# IoTKitV3th.net
KiCad netlist of a schematic drawn in EAGLE
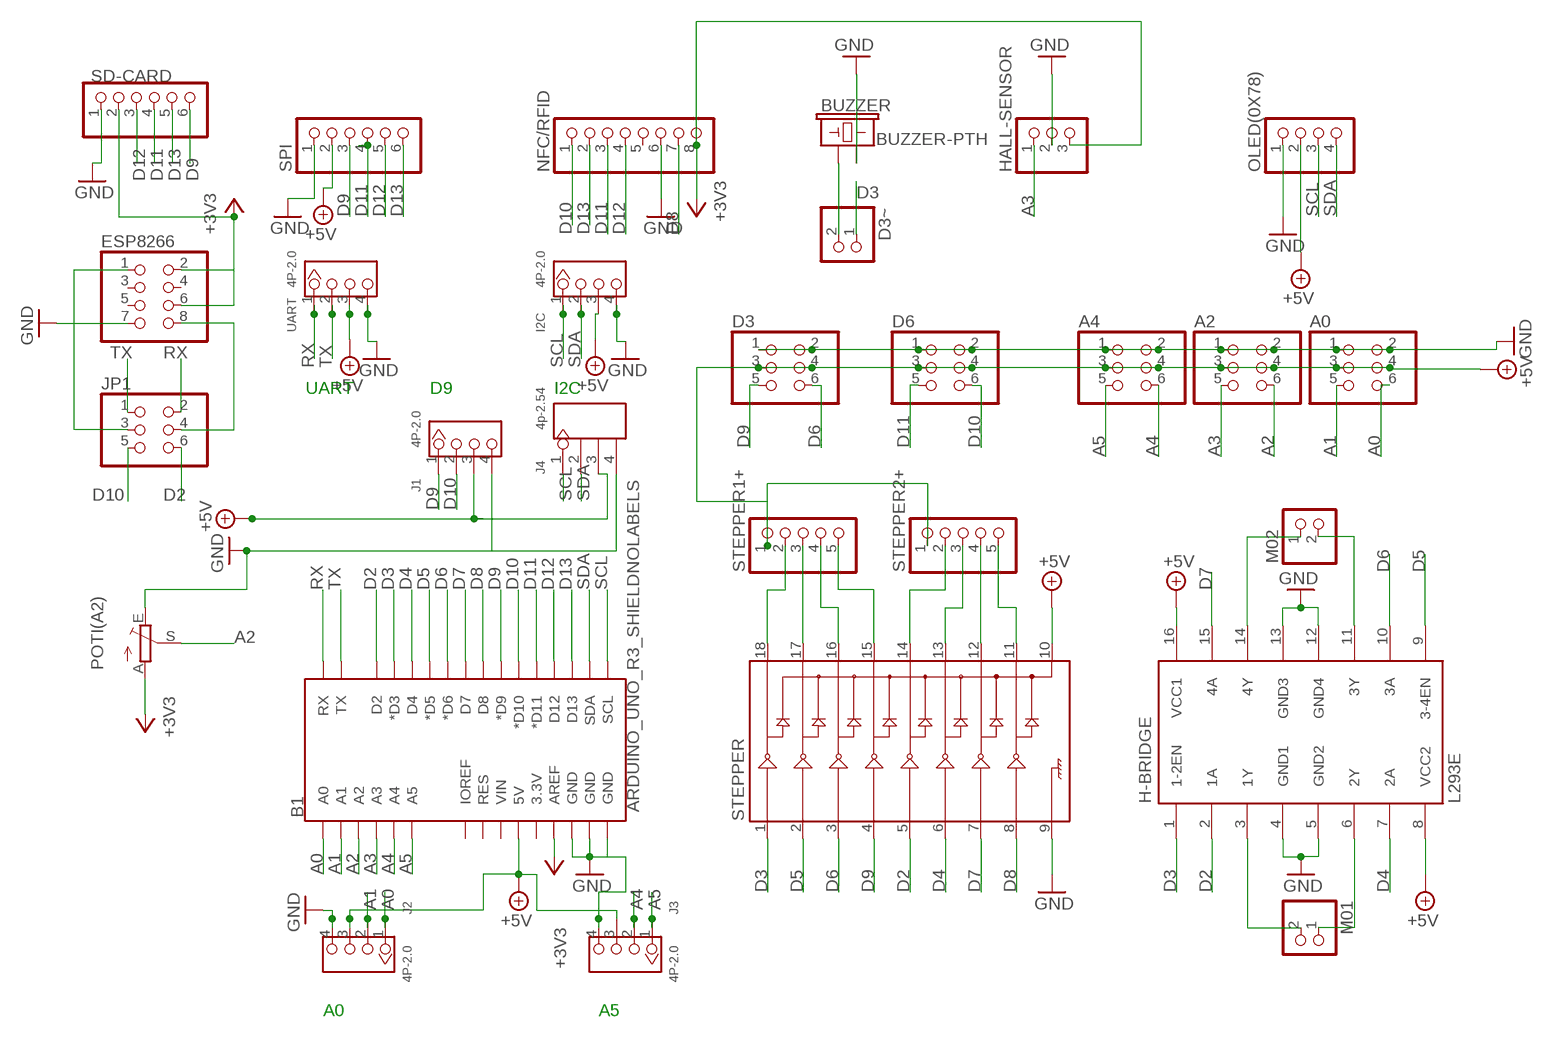
[diagram p0: schematic, sheet 1]

(export (version "E")
  (design (tool "Eeschema 10.0.6"))
  (components
    (comp (ref "A0")
      (value "PINHD-2X3")
      (footprint "eagle-import:2X03")
      (libsource (lib "eagle-import") (part "PINHD-2X3"))
    )
    (comp (ref "A2")
      (value "PINHD-2X3")
      (footprint "eagle-import:2X03")
      (libsource (lib "eagle-import") (part "PINHD-2X3"))
    )
    (comp (ref "A4")
      (value "PINHD-2X3")
      (footprint "eagle-import:2X03")
      (libsource (lib "eagle-import") (part "PINHD-2X3"))
    )
    (comp (ref "B1")
      (value "ARDUINO_UNO_R3_SHIELDNOLABELS")
      (footprint "eagle-import:UNO_R3_SHIELD_NOLABELS")
      (libsource (lib "eagle-import") (part "ARDUINO_UNO_R3_SHIELDNOLABELS"))
    )
    (comp (ref "BUZZER")
      (value "BUZZER-PTH")
      (footprint "eagle-import:BUZZER-12MM")
      (libsource (lib "eagle-import") (part "BUZZER-PTH"))
    )
    (comp (ref "D3")
      (value "PINHD-2X3")
      (footprint "eagle-import:2X03")
      (libsource (lib "eagle-import") (part "PINHD-2X3"))
    )
    (comp (ref "D3~")
      (value "PINHD-1X2")
      (footprint "eagle-import:1X02")
      (libsource (lib "eagle-import") (part "PINHD-1X2"))
    )
    (comp (ref "D6")
      (value "PINHD-2X3")
      (footprint "eagle-import:2X03")
      (libsource (lib "eagle-import") (part "PINHD-2X3"))
    )
    (comp (ref "ESP8266")
      (value "PINHD-2X4")
      (footprint "eagle-import:2X04")
      (libsource (lib "eagle-import") (part "PINHD-2X4"))
    )
    (comp (ref "H-BRIDGE")
      (value "L293E")
      (footprint "eagle-import:DIL16")
      (fields (field (name "MF") "Arrow Electronics"))
      (libsource (lib "eagle-import") (part "L293E"))
    )
    (comp (ref "HALL-SENSOR")
      (value "PINHD-1X3")
      (footprint "eagle-import:1X03")
      (libsource (lib "eagle-import") (part "PINHD-1X3"))
    )
    (comp (ref "I2C")
      (value "4P-2.0")
      (footprint "eagle-import:HW4-2.0")
      (libsource (lib "eagle-import") (part "GROVE-CONNECTOR-DIP(4P-2.0)"))
    )
    (comp (ref "J1")
      (value "4P-2.0")
      (footprint "eagle-import:HW4-2.0")
      (libsource (lib "eagle-import") (part "GROVE-CONNECTOR-DIP(4P-2.0)"))
    )
    (comp (ref "J2")
      (value "4P-2.0")
      (footprint "eagle-import:HW4-2.0")
      (libsource (lib "eagle-import") (part "GROVE-CONNECTOR-DIP(4P-2.0)"))
    )
    (comp (ref "J3")
      (value "4P-2.0")
      (footprint "eagle-import:HW4-2.0")
      (libsource (lib "eagle-import") (part "GROVE-CONNECTOR-DIP(4P-2.0)"))
    )
    (comp (ref "J4")
      (value "4p-2.54")
      (footprint "eagle-import:H4-2.54")
      (fields (field (name "MPN") "P125-1104A0BS116A1"))
      (libsource (lib "eagle-import") (part "DIP-BLACK-MALE-HEADER-VERT(4P-2.54)"))
    )
    (comp (ref "JP1")
      (value "PINHD-2X3")
      (footprint "eagle-import:2X03")
      (libsource (lib "eagle-import") (part "pinhead_325_PINHD-2X3"))
    )
    (comp (ref "M01")
      (value "PINHD-1X2")
      (footprint "eagle-import:1X02")
      (libsource (lib "eagle-import") (part "PINHD-1X2"))
    )
    (comp (ref "M02")
      (value "PINHD-1X2")
      (footprint "eagle-import:1X02")
      (libsource (lib "eagle-import") (part "PINHD-1X2"))
    )
    (comp (ref "NFC/RFID")
      (value "PINHD-1X8")
      (footprint "eagle-import:1X08")
      (libsource (lib "eagle-import") (part "PINHD-1X8"))
    )
    (comp (ref "OLED(0X78)")
      (value "PINHD-1X4")
      (footprint "eagle-import:1X04")
      (libsource (lib "eagle-import") (part "PINHD-1X4"))
    )
    (comp (ref "POTI(A2)")
      (value "TRIM_EU-B25P")
      (footprint "eagle-import:B25P")
      (libsource (lib "eagle-import") (part "TRIM_EU-B25P"))
    )
    (comp (ref "SD-CARD")
      (value "PINHD-1X6")
      (footprint "eagle-import:1X06")
      (libsource (lib "eagle-import") (part "PINHD-1X6"))
    )
    (comp (ref "SPI")
      (value "PINHD-1X6")
      (footprint "eagle-import:1X06")
      (libsource (lib "eagle-import") (part "PINHD-1X6"))
    )
    (comp (ref "STEPPER")
      (value "ULN2803DIP")
      (footprint "eagle-import:DIL18")
      (libsource (lib "eagle-import") (part "ULN2803DIP"))
    )
    (comp (ref "STEPPER1+")
      (value "PINHD-1X5")
      (footprint "eagle-import:1X05")
      (libsource (lib "eagle-import") (part "PINHD-1X5"))
    )
    (comp (ref "STEPPER2+")
      (value "PINHD-1X5")
      (footprint "eagle-import:1X05")
      (libsource (lib "eagle-import") (part "PINHD-1X5"))
    )
    (comp (ref "UART")
      (value "4P-2.0")
      (footprint "eagle-import:HW4-2.0")
      (libsource (lib "eagle-import") (part "GROVE-CONNECTOR-DIP(4P-2.0)"))
    )
  )
  (nets
    (net (code "1") (name "+3V3") (class "Default")
      (node (ref "B1") (pin "AREF") (pinfunction "AREF_AREF") (pintype "bidirectional"))
      (node (ref "ESP8266") (pin "2") (pinfunction "2_2") (pintype "passive"))
      (node (ref "ESP8266") (pin "6") (pinfunction "6_6") (pintype "passive"))
      (node (ref "HALL-SENSOR") (pin "3") (pinfunction "3_3") (pintype "passive"))
      (node (ref "NFC/RFID") (pin "8") (pinfunction "8_8") (pintype "passive"))
      (node (ref "POTI(A2)") (pin "A") (pinfunction "A_A") (pintype "passive"))
      (node (ref "SD-CARD") (pin "2") (pinfunction "2_2") (pintype "passive"))
    )
    (net (code "2") (name "+5V") (class "Default")
      (node (ref "A0") (pin "3") (pinfunction "3_3") (pintype "passive"))
      (node (ref "A0") (pin "4") (pinfunction "4_4") (pintype "passive"))
      (node (ref "A2") (pin "3") (pinfunction "3_3") (pintype "passive"))
      (node (ref "A2") (pin "4") (pinfunction "4_4") (pintype "passive"))
      (node (ref "A4") (pin "3") (pinfunction "3_3") (pintype "passive"))
      (node (ref "A4") (pin "4") (pinfunction "4_4") (pintype "passive"))
      (node (ref "B1") (pin "5V") (pinfunction "5V_5V") (pintype "bidirectional"))
      (node (ref "D3") (pin "3") (pinfunction "3_3") (pintype "passive"))
      (node (ref "D3") (pin "4") (pinfunction "4_4") (pintype "passive"))
      (node (ref "D6") (pin "3") (pinfunction "3_3") (pintype "passive"))
      (node (ref "D6") (pin "4") (pinfunction "4_4") (pintype "passive"))
      (node (ref "H-BRIDGE") (pin "16") (pinfunction "VCC1_16") (pintype "power_in"))
      (node (ref "H-BRIDGE") (pin "8") (pinfunction "VCC2_8") (pintype "power_in"))
      (node (ref "I2C") (pin "3") (pinfunction "3_3") (pintype "bidirectional"))
      (node (ref "J1") (pin "3") (pinfunction "3_3") (pintype "bidirectional"))
      (node (ref "J2") (pin "3") (pinfunction "3_3") (pintype "bidirectional"))
      (node (ref "J3") (pin "3") (pinfunction "3_3") (pintype "bidirectional"))
      (node (ref "J4") (pin "3") (pinfunction "P$3_3") (pintype "bidirectional"))
      (node (ref "OLED(0X78)") (pin "2") (pinfunction "2_2") (pintype "passive"))
      (node (ref "SPI") (pin "2") (pinfunction "2_2") (pintype "passive"))
      (node (ref "STEPPER") (pin "10") (pinfunction "10_10") (pintype "bidirectional"))
      (node (ref "STEPPER1+") (pin "1") (pinfunction "1_1") (pintype "passive"))
      (node (ref "STEPPER2+") (pin "1") (pinfunction "1_1") (pintype "passive"))
      (node (ref "UART") (pin "3") (pinfunction "3_3") (pintype "bidirectional"))
    )
    (net (code "3") (name "/A0") (class "Default")
      (node (ref "A0") (pin "6") (pinfunction "6_6") (pintype "passive"))
      (node (ref "B1") (pin "A0") (pinfunction "A0_A0") (pintype "bidirectional"))
      (node (ref "J2") (pin "1") (pinfunction "1_1") (pintype "bidirectional"))
    )
    (net (code "4") (name "/A1") (class "Default")
      (node (ref "A0") (pin "5") (pinfunction "5_5") (pintype "passive"))
      (node (ref "B1") (pin "A1") (pinfunction "A1_A1") (pintype "bidirectional"))
      (node (ref "J2") (pin "2") (pinfunction "2_2") (pintype "bidirectional"))
    )
    (net (code "5") (name "/A2") (class "Default")
      (node (ref "A2") (pin "6") (pinfunction "6_6") (pintype "passive"))
      (node (ref "B1") (pin "A2") (pinfunction "A2_A2") (pintype "bidirectional"))
      (node (ref "POTI(A2)") (pin "S") (pinfunction "S_S") (pintype "passive"))
    )
    (net (code "6") (name "/A3") (class "Default")
      (node (ref "A2") (pin "5") (pinfunction "5_5") (pintype "passive"))
      (node (ref "B1") (pin "A3") (pinfunction "A3_A3") (pintype "bidirectional"))
      (node (ref "HALL-SENSOR") (pin "1") (pinfunction "1_1") (pintype "passive"))
    )
    (net (code "7") (name "/A4") (class "Default")
      (node (ref "A4") (pin "6") (pinfunction "6_6") (pintype "passive"))
      (node (ref "B1") (pin "A4") (pinfunction "A4_A4") (pintype "bidirectional"))
      (node (ref "J3") (pin "2") (pinfunction "2_2") (pintype "bidirectional"))
    )
    (net (code "8") (name "/A5") (class "Default")
      (node (ref "A4") (pin "5") (pinfunction "5_5") (pintype "passive"))
      (node (ref "B1") (pin "A5") (pinfunction "A5_A5") (pintype "bidirectional"))
      (node (ref "J3") (pin "1") (pinfunction "1_1") (pintype "bidirectional"))
    )
    (net (code "9") (name "/D2") (class "Default")
      (node (ref "B1") (pin "D2") (pinfunction "D2_D2") (pintype "bidirectional"))
      (node (ref "H-BRIDGE") (pin "2") (pinfunction "1A_2") (pintype "input"))
      (node (ref "JP1") (pin "6") (pinfunction "6_6") (pintype "passive"))
      (node (ref "STEPPER") (pin "5") (pinfunction "5_5") (pintype "bidirectional"))
    )
    (net (code "10") (name "/D3") (class "Default")
      (node (ref "B1") (pin "D3") (pinfunction "*D3_D3") (pintype "bidirectional"))
      (node (ref "D3~") (pin "1") (pinfunction "1_1") (pintype "passive"))
      (node (ref "H-BRIDGE") (pin "1") (pinfunction "1-2EN_1") (pintype "input"))
      (node (ref "STEPPER") (pin "1") (pinfunction "1_1") (pintype "bidirectional"))
    )
    (net (code "11") (name "/D4") (class "Default")
      (node (ref "B1") (pin "D4") (pinfunction "D4_D4") (pintype "bidirectional"))
      (node (ref "H-BRIDGE") (pin "7") (pinfunction "2A_7") (pintype "input"))
      (node (ref "STEPPER") (pin "6") (pinfunction "6_6") (pintype "bidirectional"))
    )
    (net (code "12") (name "/D5") (class "Default")
      (node (ref "B1") (pin "D5") (pinfunction "*D5_D5") (pintype "bidirectional"))
      (node (ref "H-BRIDGE") (pin "9") (pinfunction "3-4EN_9") (pintype "input"))
      (node (ref "STEPPER") (pin "2") (pinfunction "2_2") (pintype "bidirectional"))
    )
    (net (code "13") (name "/D6") (class "Default")
      (node (ref "B1") (pin "D6") (pinfunction "*D6_D6") (pintype "bidirectional"))
      (node (ref "D3") (pin "6") (pinfunction "6_6") (pintype "passive"))
      (node (ref "H-BRIDGE") (pin "10") (pinfunction "3A_10") (pintype "input"))
      (node (ref "STEPPER") (pin "3") (pinfunction "3_3") (pintype "bidirectional"))
    )
    (net (code "14") (name "/D7") (class "Default")
      (node (ref "B1") (pin "D7") (pinfunction "D7_D7") (pintype "bidirectional"))
      (node (ref "H-BRIDGE") (pin "15") (pinfunction "4A_15") (pintype "input"))
      (node (ref "STEPPER") (pin "7") (pinfunction "7_7") (pintype "bidirectional"))
    )
    (net (code "15") (name "/D8") (class "Default")
      (node (ref "B1") (pin "D8") (pinfunction "D8_D8") (pintype "bidirectional"))
      (node (ref "NFC/RFID") (pin "7") (pinfunction "7_7") (pintype "passive"))
      (node (ref "STEPPER") (pin "8") (pinfunction "8_8") (pintype "bidirectional"))
    )
    (net (code "16") (name "/D9") (class "Default")
      (node (ref "B1") (pin "D9") (pinfunction "*D9_D9") (pintype "bidirectional"))
      (node (ref "D3") (pin "5") (pinfunction "5_5") (pintype "passive"))
      (node (ref "J1") (pin "1") (pinfunction "1_1") (pintype "bidirectional"))
      (node (ref "SD-CARD") (pin "6") (pinfunction "6_6") (pintype "passive"))
      (node (ref "SPI") (pin "3") (pinfunction "3_3") (pintype "passive"))
      (node (ref "STEPPER") (pin "4") (pinfunction "4_4") (pintype "bidirectional"))
    )
    (net (code "17") (name "/D10") (class "Default")
      (node (ref "B1") (pin "D10") (pinfunction "*D10_D10") (pintype "bidirectional"))
      (node (ref "D6") (pin "6") (pinfunction "6_6") (pintype "passive"))
      (node (ref "J1") (pin "2") (pinfunction "2_2") (pintype "bidirectional"))
      (node (ref "JP1") (pin "5") (pinfunction "5_5") (pintype "passive"))
      (node (ref "NFC/RFID") (pin "1") (pinfunction "1_1") (pintype "passive"))
    )
    (net (code "18") (name "/D11") (class "Default")
      (node (ref "B1") (pin "D11") (pinfunction "*D11_D11") (pintype "bidirectional"))
      (node (ref "D6") (pin "5") (pinfunction "5_5") (pintype "passive"))
      (node (ref "NFC/RFID") (pin "3") (pinfunction "3_3") (pintype "passive"))
      (node (ref "SD-CARD") (pin "4") (pinfunction "4_4") (pintype "passive"))
      (node (ref "SPI") (pin "4") (pinfunction "4_4") (pintype "passive"))
    )
    (net (code "19") (name "/D12") (class "Default")
      (node (ref "B1") (pin "D12") (pinfunction "D12_D12") (pintype "bidirectional"))
      (node (ref "NFC/RFID") (pin "4") (pinfunction "4_4") (pintype "passive"))
      (node (ref "SD-CARD") (pin "3") (pinfunction "3_3") (pintype "passive"))
      (node (ref "SPI") (pin "5") (pinfunction "5_5") (pintype "passive"))
    )
    (net (code "20") (name "/D13") (class "Default")
      (node (ref "B1") (pin "D13") (pinfunction "D13_D13") (pintype "bidirectional"))
      (node (ref "NFC/RFID") (pin "2") (pinfunction "2_2") (pintype "passive"))
      (node (ref "SD-CARD") (pin "5") (pinfunction "5_5") (pintype "passive"))
      (node (ref "SPI") (pin "6") (pinfunction "6_6") (pintype "passive"))
    )
    (net (code "21") (name "/RX") (class "Default")
      (node (ref "B1") (pin "RX") (pinfunction "RX_RX") (pintype "bidirectional"))
      (node (ref "JP1") (pin "2") (pinfunction "2_2") (pintype "passive"))
      (node (ref "UART") (pin "1") (pinfunction "1_1") (pintype "bidirectional"))
    )
    (net (code "22") (name "/SCL") (class "Default")
      (node (ref "B1") (pin "SCL") (pinfunction "SCL_SCL") (pintype "bidirectional"))
      (node (ref "I2C") (pin "1") (pinfunction "1_1") (pintype "bidirectional"))
      (node (ref "J4") (pin "1") (pinfunction "P$1_1") (pintype "bidirectional"))
      (node (ref "OLED(0X78)") (pin "3") (pinfunction "3_3") (pintype "passive"))
    )
    (net (code "23") (name "/SDA") (class "Default")
      (node (ref "B1") (pin "SDA") (pinfunction "SDA_SDA") (pintype "bidirectional"))
      (node (ref "I2C") (pin "2") (pinfunction "2_2") (pintype "bidirectional"))
      (node (ref "J4") (pin "2") (pinfunction "P$2_2") (pintype "bidirectional"))
      (node (ref "OLED(0X78)") (pin "4") (pinfunction "4_4") (pintype "passive"))
    )
    (net (code "24") (name "/TX") (class "Default")
      (node (ref "B1") (pin "TX") (pinfunction "TX_TX") (pintype "bidirectional"))
      (node (ref "JP1") (pin "1") (pinfunction "1_1") (pintype "passive"))
      (node (ref "UART") (pin "2") (pinfunction "2_2") (pintype "bidirectional"))
    )
    (net (code "25") (name "GND") (class "Default")
      (node (ref "A0") (pin "1") (pinfunction "1_1") (pintype "passive"))
      (node (ref "A0") (pin "2") (pinfunction "2_2") (pintype "passive"))
      (node (ref "A2") (pin "1") (pinfunction "1_1") (pintype "passive"))
      (node (ref "A2") (pin "2") (pinfunction "2_2") (pintype "passive"))
      (node (ref "A4") (pin "1") (pinfunction "1_1") (pintype "passive"))
      (node (ref "A4") (pin "2") (pinfunction "2_2") (pintype "passive"))
      (node (ref "B1") (pin "GND@0") (pinfunction "GND_GND@0") (pintype "bidirectional"))
      (node (ref "B1") (pin "GND@1") (pinfunction "GND_GND@1") (pintype "bidirectional"))
      (node (ref "B1") (pin "GND@2") (pinfunction "GND_GND@2") (pintype "bidirectional"))
      (node (ref "BUZZER") (pin "-") (pinfunction "2_-") (pintype "passive"))
      (node (ref "D3") (pin "1") (pinfunction "1_1") (pintype "passive"))
      (node (ref "D3") (pin "2") (pinfunction "2_2") (pintype "passive"))
      (node (ref "D6") (pin "1") (pinfunction "1_1") (pintype "passive"))
      (node (ref "D6") (pin "2") (pinfunction "2_2") (pintype "passive"))
      (node (ref "ESP8266") (pin "7") (pinfunction "7_7") (pintype "passive"))
      (node (ref "H-BRIDGE") (pin "12") (pinfunction "GND4_12") (pintype "power_in"))
      (node (ref "H-BRIDGE") (pin "13") (pinfunction "GND3_13") (pintype "power_in"))
      (node (ref "H-BRIDGE") (pin "4") (pinfunction "GND1_4") (pintype "power_in"))
      (node (ref "H-BRIDGE") (pin "5") (pinfunction "GND2_5") (pintype "power_in"))
      (node (ref "HALL-SENSOR") (pin "2") (pinfunction "2_2") (pintype "passive"))
      (node (ref "I2C") (pin "4") (pinfunction "4_4") (pintype "bidirectional"))
      (node (ref "J1") (pin "4") (pinfunction "4_4") (pintype "bidirectional"))
      (node (ref "J2") (pin "4") (pinfunction "4_4") (pintype "bidirectional"))
      (node (ref "J3") (pin "4") (pinfunction "4_4") (pintype "bidirectional"))
      (node (ref "J4") (pin "4") (pinfunction "P$4_4") (pintype "bidirectional"))
      (node (ref "NFC/RFID") (pin "6") (pinfunction "6_6") (pintype "passive"))
      (node (ref "OLED(0X78)") (pin "1") (pinfunction "1_1") (pintype "passive"))
      (node (ref "POTI(A2)") (pin "E") (pinfunction "E_E") (pintype "passive"))
      (node (ref "SD-CARD") (pin "1") (pinfunction "1_1") (pintype "passive"))
      (node (ref "SPI") (pin "1") (pinfunction "1_1") (pintype "passive"))
      (node (ref "STEPPER") (pin "9") (pinfunction "9_9") (pintype "bidirectional"))
      (node (ref "UART") (pin "4") (pinfunction "4_4") (pintype "bidirectional"))
    )
    (net (code "26") (name "Net-(BUZZER-1)") (class "Default")
      (node (ref "BUZZER") (pin "+") (pinfunction "1_+") (pintype "passive"))
      (node (ref "D3~") (pin "2") (pinfunction "2_2") (pintype "passive"))
    )
    (net (code "27") (name "Net-(ESP8266-Pad1)") (class "Default")
      (node (ref "ESP8266") (pin "1") (pinfunction "1_1") (pintype "passive"))
      (node (ref "JP1") (pin "3") (pinfunction "3_3") (pintype "passive"))
    )
    (net (code "28") (name "Net-(ESP8266-Pad8)") (class "Default")
      (node (ref "ESP8266") (pin "8") (pinfunction "8_8") (pintype "passive"))
      (node (ref "JP1") (pin "4") (pinfunction "4_4") (pintype "passive"))
    )
    (net (code "29") (name "Net-(H-BRIDGE-1Y)") (class "Default")
      (node (ref "H-BRIDGE") (pin "3") (pinfunction "1Y_3") (pintype "output"))
      (node (ref "M01") (pin "2") (pinfunction "2_2") (pintype "passive"))
    )
    (net (code "30") (name "Net-(H-BRIDGE-2Y)") (class "Default")
      (node (ref "H-BRIDGE") (pin "6") (pinfunction "2Y_6") (pintype "output"))
      (node (ref "M01") (pin "1") (pinfunction "1_1") (pintype "passive"))
    )
    (net (code "31") (name "Net-(H-BRIDGE-3Y)") (class "Default")
      (node (ref "H-BRIDGE") (pin "11") (pinfunction "3Y_11") (pintype "output"))
      (node (ref "M02") (pin "2") (pinfunction "2_2") (pintype "passive"))
    )
    (net (code "32") (name "Net-(H-BRIDGE-4Y)") (class "Default")
      (node (ref "H-BRIDGE") (pin "14") (pinfunction "4Y_14") (pintype "output"))
      (node (ref "M02") (pin "1") (pinfunction "1_1") (pintype "passive"))
    )
    (net (code "33") (name "Net-(STEPPER-Pad11)") (class "Default")
      (node (ref "STEPPER") (pin "11") (pinfunction "11_11") (pintype "bidirectional"))
      (node (ref "STEPPER2+") (pin "5") (pinfunction "5_5") (pintype "passive"))
    )
    (net (code "34") (name "Net-(STEPPER-Pad12)") (class "Default")
      (node (ref "STEPPER") (pin "12") (pinfunction "12_12") (pintype "bidirectional"))
      (node (ref "STEPPER2+") (pin "4") (pinfunction "4_4") (pintype "passive"))
    )
    (net (code "35") (name "Net-(STEPPER-Pad13)") (class "Default")
      (node (ref "STEPPER") (pin "13") (pinfunction "13_13") (pintype "bidirectional"))
      (node (ref "STEPPER2+") (pin "3") (pinfunction "3_3") (pintype "passive"))
    )
    (net (code "36") (name "Net-(STEPPER-Pad14)") (class "Default")
      (node (ref "STEPPER") (pin "14") (pinfunction "14_14") (pintype "bidirectional"))
      (node (ref "STEPPER2+") (pin "2") (pinfunction "2_2") (pintype "passive"))
    )
    (net (code "37") (name "Net-(STEPPER-Pad15)") (class "Default")
      (node (ref "STEPPER") (pin "15") (pinfunction "15_15") (pintype "bidirectional"))
      (node (ref "STEPPER1+") (pin "5") (pinfunction "5_5") (pintype "passive"))
    )
    (net (code "38") (name "Net-(STEPPER-Pad16)") (class "Default")
      (node (ref "STEPPER") (pin "16") (pinfunction "16_16") (pintype "bidirectional"))
      (node (ref "STEPPER1+") (pin "4") (pinfunction "4_4") (pintype "passive"))
    )
    (net (code "39") (name "Net-(STEPPER-Pad17)") (class "Default")
      (node (ref "STEPPER") (pin "17") (pinfunction "17_17") (pintype "bidirectional"))
      (node (ref "STEPPER1+") (pin "3") (pinfunction "3_3") (pintype "passive"))
    )
    (net (code "40") (name "Net-(STEPPER-Pad18)") (class "Default")
      (node (ref "STEPPER") (pin "18") (pinfunction "18_18") (pintype "bidirectional"))
      (node (ref "STEPPER1+") (pin "2") (pinfunction "2_2") (pintype "passive"))
    )
    (net (code "41") (name "unconnected-(B1-Pad3.3V)") (class "Default")
      (node (ref "B1") (pin "3.3V") (pinfunction "3.3V_3.3V") (pintype "bidirectional"))
    )
    (net (code "42") (name "unconnected-(B1-PadIOREF)") (class "Default")
      (node (ref "B1") (pin "IOREF") (pinfunction "IOREF_IOREF") (pintype "bidirectional"))
    )
    (net (code "43") (name "unconnected-(B1-PadRES)") (class "Default")
      (node (ref "B1") (pin "RES") (pinfunction "RES_RES") (pintype "bidirectional"))
    )
    (net (code "44") (name "unconnected-(B1-PadVIN)") (class "Default")
      (node (ref "B1") (pin "VIN") (pinfunction "VIN_VIN") (pintype "bidirectional"))
    )
    (net (code "45") (name "unconnected-(ESP8266-Pad3)") (class "Default")
      (node (ref "ESP8266") (pin "3") (pinfunction "3_3") (pintype "passive"))
    )
    (net (code "46") (name "unconnected-(ESP8266-Pad4)") (class "Default")
      (node (ref "ESP8266") (pin "4") (pinfunction "4_4") (pintype "passive"))
    )
    (net (code "47") (name "unconnected-(ESP8266-Pad5)") (class "Default")
      (node (ref "ESP8266") (pin "5") (pinfunction "5_5") (pintype "passive"))
    )
    (net (code "48") (name "unconnected-(NFC/RFID-Pad5)") (class "Default")
      (node (ref "NFC/RFID") (pin "5") (pinfunction "5_5") (pintype "passive"))
    )
  )
)
